# aparture_v1.net
KiCad netlist of a schematic drawn in EAGLE
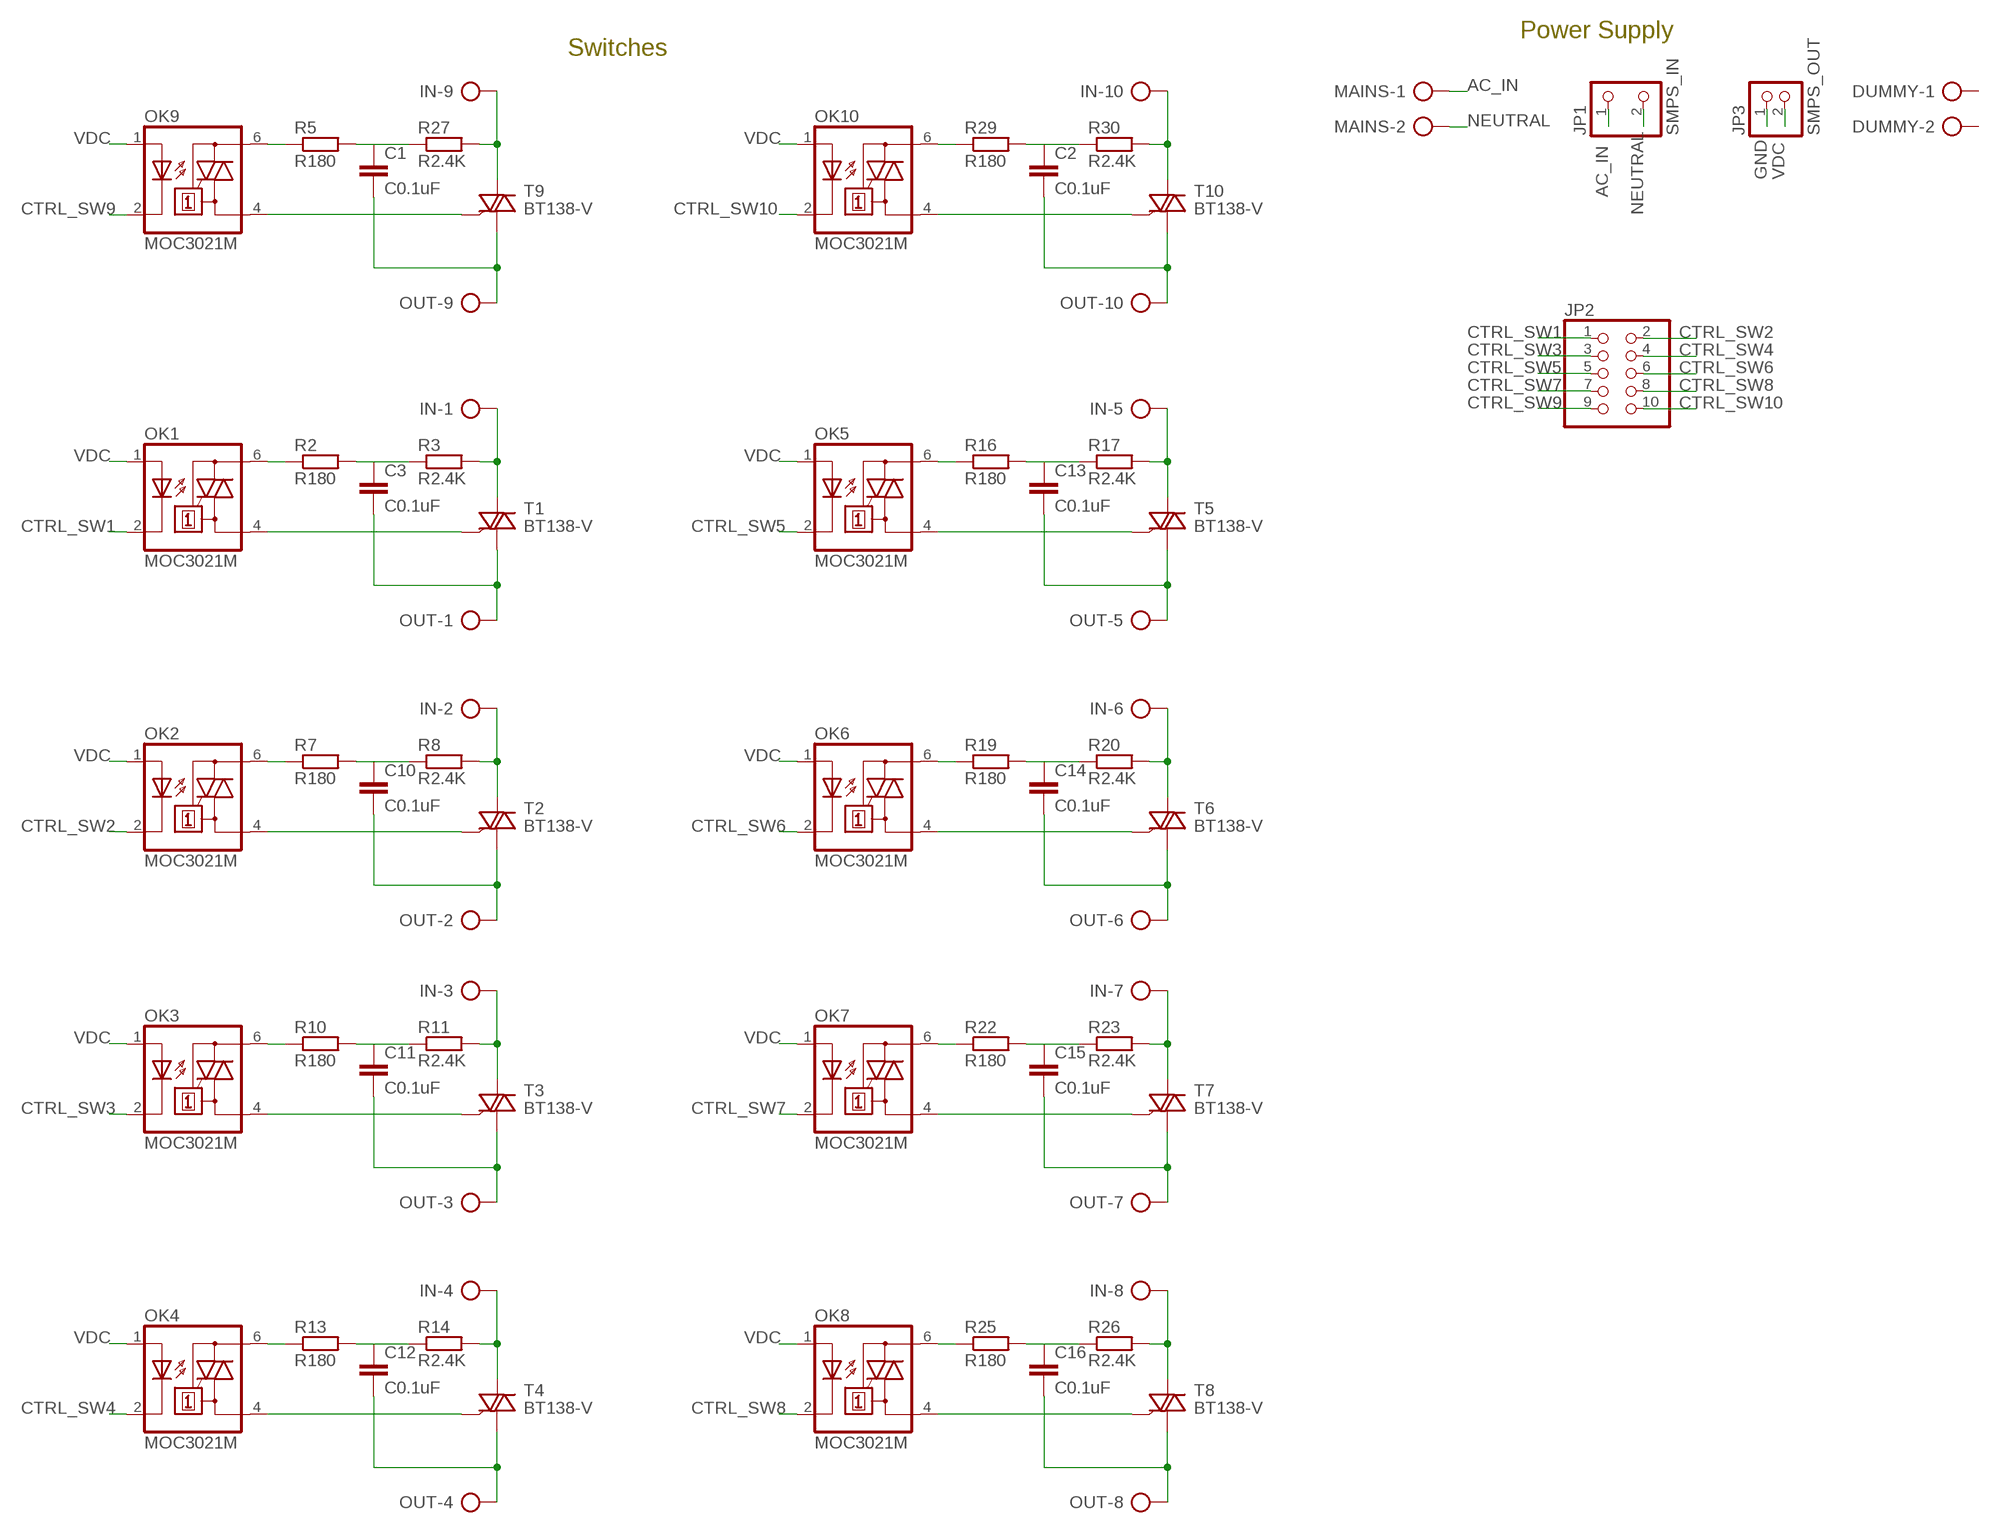
[diagram p0: schematic, sheet 1]

(export (version "E")
  (design (tool "Eeschema 10.0.6"))
  (components
    (comp (ref "C1")
      (value "C0.1uF")
      (footprint "eagle-import:C0805")
      (libsource (lib "eagle-import") (part "C-EUC0805"))
    )
    (comp (ref "C2")
      (value "C0.1uF")
      (footprint "eagle-import:C0805")
      (libsource (lib "eagle-import") (part "C-EUC0805"))
    )
    (comp (ref "C3")
      (value "C0.1uF")
      (footprint "eagle-import:C0805")
      (libsource (lib "eagle-import") (part "C-EUC0805"))
    )
    (comp (ref "C10")
      (value "C0.1uF")
      (footprint "eagle-import:C0805")
      (libsource (lib "eagle-import") (part "C-EUC0805"))
    )
    (comp (ref "C11")
      (value "C0.1uF")
      (footprint "eagle-import:C0805")
      (libsource (lib "eagle-import") (part "C-EUC0805"))
    )
    (comp (ref "C12")
      (value "C0.1uF")
      (footprint "eagle-import:C0805")
      (libsource (lib "eagle-import") (part "C-EUC0805"))
    )
    (comp (ref "C13")
      (value "C0.1uF")
      (footprint "eagle-import:C0805")
      (libsource (lib "eagle-import") (part "C-EUC0805"))
    )
    (comp (ref "C14")
      (value "C0.1uF")
      (footprint "eagle-import:C0805")
      (libsource (lib "eagle-import") (part "C-EUC0805"))
    )
    (comp (ref "C15")
      (value "C0.1uF")
      (footprint "eagle-import:C0805")
      (libsource (lib "eagle-import") (part "C-EUC0805"))
    )
    (comp (ref "C16")
      (value "C0.1uF")
      (footprint "eagle-import:C0805")
      (libsource (lib "eagle-import") (part "C-EUC0805"))
    )
    (comp (ref "DUMMY")
      (value "AK300/2")
      (footprint "eagle-import:AK300_2")
      (fields (field (name "OC_FARNELL") "unknown") (field (name "OC_NEWARK") "unknown"))
      (libsource (lib "eagle-import") (part "AK300/2"))
    )
    (comp (ref "IN")
      (value "AK300/10")
      (footprint "eagle-import:AK300_10")
      (libsource (lib "eagle-import") (part "AK300/10"))
    )
    (comp (ref "JP1")
      (value "SMPS_IN")
      (footprint "eagle-import:SMPS_IN")
      (libsource (lib "eagle-import") (part "SMPS_IN"))
    )
    (comp (ref "JP2")
      (value "PINHD-2X5")
      (footprint "eagle-import:2X05")
      (libsource (lib "eagle-import") (part "PINHD-2X5"))
    )
    (comp (ref "JP3")
      (value "SMPS_OUT")
      (footprint "eagle-import:1X02")
      (libsource (lib "eagle-import") (part "PINHD-1X2"))
    )
    (comp (ref "MAINS")
      (value "AK300/2")
      (footprint "eagle-import:AK300_2")
      (libsource (lib "eagle-import") (part "AK300/2"))
    )
    (comp (ref "OK1")
      (value "MOC3021M")
      (footprint "eagle-import:DIL06")
      (fields (field (name "MF") "FAIRCHILD SEMICONDUCTOR") (field (name "MPN") "MOC3021-M"))
      (libsource (lib "eagle-import") (part "MOC30M21"))
    )
    (comp (ref "OK2")
      (value "MOC3021M")
      (footprint "eagle-import:DIL06")
      (fields (field (name "MF") "FAIRCHILD SEMICONDUCTOR") (field (name "MPN") "MOC3021-M"))
      (libsource (lib "eagle-import") (part "MOC30M21"))
    )
    (comp (ref "OK3")
      (value "MOC3021M")
      (footprint "eagle-import:DIL06")
      (fields (field (name "MF") "FAIRCHILD SEMICONDUCTOR") (field (name "MPN") "MOC3021-M"))
      (libsource (lib "eagle-import") (part "MOC30M21"))
    )
    (comp (ref "OK4")
      (value "MOC3021M")
      (footprint "eagle-import:DIL06")
      (fields (field (name "MF") "FAIRCHILD SEMICONDUCTOR") (field (name "MPN") "MOC3021-M"))
      (libsource (lib "eagle-import") (part "MOC30M21"))
    )
    (comp (ref "OK5")
      (value "MOC3021M")
      (footprint "eagle-import:DIL06")
      (fields (field (name "MF") "FAIRCHILD SEMICONDUCTOR") (field (name "MPN") "MOC3021-M"))
      (libsource (lib "eagle-import") (part "MOC30M21"))
    )
    (comp (ref "OK6")
      (value "MOC3021M")
      (footprint "eagle-import:DIL06")
      (fields (field (name "MF") "FAIRCHILD SEMICONDUCTOR") (field (name "MPN") "MOC3021-M"))
      (libsource (lib "eagle-import") (part "MOC30M21"))
    )
    (comp (ref "OK7")
      (value "MOC3021M")
      (footprint "eagle-import:DIL06")
      (fields (field (name "MF") "FAIRCHILD SEMICONDUCTOR") (field (name "MPN") "MOC3021-M"))
      (libsource (lib "eagle-import") (part "MOC30M21"))
    )
    (comp (ref "OK8")
      (value "MOC3021M")
      (footprint "eagle-import:DIL06")
      (fields (field (name "MF") "FAIRCHILD SEMICONDUCTOR") (field (name "MPN") "MOC3021-M"))
      (libsource (lib "eagle-import") (part "MOC30M21"))
    )
    (comp (ref "OK9")
      (value "MOC3021M")
      (footprint "eagle-import:DIL06")
      (fields (field (name "MF") "FAIRCHILD SEMICONDUCTOR") (field (name "MPN") "MOC3021-M"))
      (libsource (lib "eagle-import") (part "MOC30M21"))
    )
    (comp (ref "OK10")
      (value "MOC3021M")
      (footprint "eagle-import:DIL06")
      (fields (field (name "MF") "FAIRCHILD SEMICONDUCTOR") (field (name "MPN") "MOC3021-M"))
      (libsource (lib "eagle-import") (part "MOC30M21"))
    )
    (comp (ref "OUT")
      (value "AK300/10")
      (footprint "eagle-import:AK300_10")
      (libsource (lib "eagle-import") (part "AK300/10"))
    )
    (comp (ref "R2")
      (value "R180")
      (footprint "eagle-import:M0805")
      (libsource (lib "eagle-import") (part "R-EU_M0805"))
    )
    (comp (ref "R3")
      (value "R2.4K")
      (footprint "eagle-import:M0805")
      (libsource (lib "eagle-import") (part "R-EU_M0805"))
    )
    (comp (ref "R5")
      (value "R180")
      (footprint "eagle-import:M0805")
      (libsource (lib "eagle-import") (part "R-EU_M0805"))
    )
    (comp (ref "R7")
      (value "R180")
      (footprint "eagle-import:M0805")
      (libsource (lib "eagle-import") (part "R-EU_M0805"))
    )
    (comp (ref "R8")
      (value "R2.4K")
      (footprint "eagle-import:M0805")
      (libsource (lib "eagle-import") (part "R-EU_M0805"))
    )
    (comp (ref "R10")
      (value "R180")
      (footprint "eagle-import:M0805")
      (libsource (lib "eagle-import") (part "R-EU_M0805"))
    )
    (comp (ref "R11")
      (value "R2.4K")
      (footprint "eagle-import:M0805")
      (libsource (lib "eagle-import") (part "R-EU_M0805"))
    )
    (comp (ref "R13")
      (value "R180")
      (footprint "eagle-import:M0805")
      (libsource (lib "eagle-import") (part "R-EU_M0805"))
    )
    (comp (ref "R14")
      (value "R2.4K")
      (footprint "eagle-import:M0805")
      (libsource (lib "eagle-import") (part "R-EU_M0805"))
    )
    (comp (ref "R16")
      (value "R180")
      (footprint "eagle-import:M0805")
      (libsource (lib "eagle-import") (part "R-EU_M0805"))
    )
    (comp (ref "R17")
      (value "R2.4K")
      (footprint "eagle-import:M0805")
      (libsource (lib "eagle-import") (part "R-EU_M0805"))
    )
    (comp (ref "R19")
      (value "R180")
      (footprint "eagle-import:M0805")
      (libsource (lib "eagle-import") (part "R-EU_M0805"))
    )
    (comp (ref "R20")
      (value "R2.4K")
      (footprint "eagle-import:M0805")
      (libsource (lib "eagle-import") (part "R-EU_M0805"))
    )
    (comp (ref "R22")
      (value "R180")
      (footprint "eagle-import:M0805")
      (libsource (lib "eagle-import") (part "R-EU_M0805"))
    )
    (comp (ref "R23")
      (value "R2.4K")
      (footprint "eagle-import:M0805")
      (libsource (lib "eagle-import") (part "R-EU_M0805"))
    )
    (comp (ref "R25")
      (value "R180")
      (footprint "eagle-import:M0805")
      (libsource (lib "eagle-import") (part "R-EU_M0805"))
    )
    (comp (ref "R26")
      (value "R2.4K")
      (footprint "eagle-import:M0805")
      (libsource (lib "eagle-import") (part "R-EU_M0805"))
    )
    (comp (ref "R27")
      (value "R2.4K")
      (footprint "eagle-import:M0805")
      (libsource (lib "eagle-import") (part "R-EU_M0805"))
    )
    (comp (ref "R29")
      (value "R180")
      (footprint "eagle-import:M0805")
      (libsource (lib "eagle-import") (part "R-EU_M0805"))
    )
    (comp (ref "R30")
      (value "R2.4K")
      (footprint "eagle-import:M0805")
      (libsource (lib "eagle-import") (part "R-EU_M0805"))
    )
    (comp (ref "T1")
      (value "BT138-V")
      (footprint "eagle-import:TO220BV")
      (libsource (lib "eagle-import") (part "BT138-V"))
    )
    (comp (ref "T2")
      (value "BT138-V")
      (footprint "eagle-import:TO220BV")
      (libsource (lib "eagle-import") (part "BT138-V"))
    )
    (comp (ref "T3")
      (value "BT138-V")
      (footprint "eagle-import:TO220BV")
      (libsource (lib "eagle-import") (part "BT138-V"))
    )
    (comp (ref "T4")
      (value "BT138-V")
      (footprint "eagle-import:TO220BV")
      (libsource (lib "eagle-import") (part "BT138-V"))
    )
    (comp (ref "T5")
      (value "BT138-V")
      (footprint "eagle-import:TO220BV")
      (libsource (lib "eagle-import") (part "BT138-V"))
    )
    (comp (ref "T6")
      (value "BT138-V")
      (footprint "eagle-import:TO220BV")
      (libsource (lib "eagle-import") (part "BT138-V"))
    )
    (comp (ref "T7")
      (value "BT138-V")
      (footprint "eagle-import:TO220BV")
      (libsource (lib "eagle-import") (part "BT138-V"))
    )
    (comp (ref "T8")
      (value "BT138-V")
      (footprint "eagle-import:TO220BV")
      (libsource (lib "eagle-import") (part "BT138-V"))
    )
    (comp (ref "T9")
      (value "BT138-V")
      (footprint "eagle-import:TO220BV")
      (libsource (lib "eagle-import") (part "BT138-V"))
    )
    (comp (ref "T10")
      (value "BT138-V")
      (footprint "eagle-import:TO220BV")
      (libsource (lib "eagle-import") (part "BT138-V"))
    )
  )
  (nets
    (net (code "1") (name "/AC_IN") (class "Default")
      (node (ref "JP1") (pin "1") (pinfunction "1_1") (pintype "passive"))
      (node (ref "MAINS") (pin "1") (pinfunction "KL_1") (pintype "passive"))
    )
    (net (code "2") (name "/CTRL_SW1") (class "Default")
      (node (ref "JP2") (pin "1") (pinfunction "1_1") (pintype "passive"))
      (node (ref "OK1") (pin "2") (pinfunction "C_2") (pintype "passive"))
    )
    (net (code "3") (name "/CTRL_SW2") (class "Default")
      (node (ref "JP2") (pin "2") (pinfunction "2_2") (pintype "passive"))
      (node (ref "OK2") (pin "2") (pinfunction "C_2") (pintype "passive"))
    )
    (net (code "4") (name "/CTRL_SW3") (class "Default")
      (node (ref "JP2") (pin "3") (pinfunction "3_3") (pintype "passive"))
      (node (ref "OK3") (pin "2") (pinfunction "C_2") (pintype "passive"))
    )
    (net (code "5") (name "/CTRL_SW4") (class "Default")
      (node (ref "JP2") (pin "4") (pinfunction "4_4") (pintype "passive"))
      (node (ref "OK4") (pin "2") (pinfunction "C_2") (pintype "passive"))
    )
    (net (code "6") (name "/CTRL_SW5") (class "Default")
      (node (ref "JP2") (pin "5") (pinfunction "5_5") (pintype "passive"))
      (node (ref "OK5") (pin "2") (pinfunction "C_2") (pintype "passive"))
    )
    (net (code "7") (name "/CTRL_SW6") (class "Default")
      (node (ref "JP2") (pin "6") (pinfunction "6_6") (pintype "passive"))
      (node (ref "OK6") (pin "2") (pinfunction "C_2") (pintype "passive"))
    )
    (net (code "8") (name "/CTRL_SW7") (class "Default")
      (node (ref "JP2") (pin "7") (pinfunction "7_7") (pintype "passive"))
      (node (ref "OK7") (pin "2") (pinfunction "C_2") (pintype "passive"))
    )
    (net (code "9") (name "/CTRL_SW8") (class "Default")
      (node (ref "JP2") (pin "8") (pinfunction "8_8") (pintype "passive"))
      (node (ref "OK8") (pin "2") (pinfunction "C_2") (pintype "passive"))
    )
    (net (code "10") (name "/CTRL_SW9") (class "Default")
      (node (ref "JP2") (pin "9") (pinfunction "9_9") (pintype "passive"))
      (node (ref "OK9") (pin "2") (pinfunction "C_2") (pintype "passive"))
    )
    (net (code "11") (name "/CTRL_SW10") (class "Default")
      (node (ref "JP2") (pin "10") (pinfunction "10_10") (pintype "passive"))
      (node (ref "OK10") (pin "2") (pinfunction "C_2") (pintype "passive"))
    )
    (net (code "12") (name "/GND") (class "Default")
      (node (ref "JP3") (pin "1") (pinfunction "1_1") (pintype "passive"))
    )
    (net (code "13") (name "/NEUTRAL") (class "Default")
      (node (ref "JP1") (pin "2") (pinfunction "2_2") (pintype "passive"))
      (node (ref "MAINS") (pin "2") (pinfunction "KL_2") (pintype "passive"))
    )
    (net (code "14") (name "/VDC") (class "Default")
      (node (ref "JP3") (pin "2") (pinfunction "2_2") (pintype "passive"))
      (node (ref "OK1") (pin "1") (pinfunction "A_1") (pintype "passive"))
      (node (ref "OK10") (pin "1") (pinfunction "A_1") (pintype "passive"))
      (node (ref "OK2") (pin "1") (pinfunction "A_1") (pintype "passive"))
      (node (ref "OK3") (pin "1") (pinfunction "A_1") (pintype "passive"))
      (node (ref "OK4") (pin "1") (pinfunction "A_1") (pintype "passive"))
      (node (ref "OK5") (pin "1") (pinfunction "A_1") (pintype "passive"))
      (node (ref "OK6") (pin "1") (pinfunction "A_1") (pintype "passive"))
      (node (ref "OK7") (pin "1") (pinfunction "A_1") (pintype "passive"))
      (node (ref "OK8") (pin "1") (pinfunction "A_1") (pintype "passive"))
      (node (ref "OK9") (pin "1") (pinfunction "A_1") (pintype "passive"))
    )
    (net (code "15") (name "Net-(C1-Pad1)") (class "Default")
      (node (ref "C1") (pin "1") (pinfunction "1_1") (pintype "passive"))
      (node (ref "R27") (pin "1") (pinfunction "1_1") (pintype "passive"))
      (node (ref "R5") (pin "2") (pinfunction "2_2") (pintype "passive"))
    )
    (net (code "16") (name "Net-(C2-Pad1)") (class "Default")
      (node (ref "C2") (pin "1") (pinfunction "1_1") (pintype "passive"))
      (node (ref "R29") (pin "2") (pinfunction "2_2") (pintype "passive"))
      (node (ref "R30") (pin "1") (pinfunction "1_1") (pintype "passive"))
    )
    (net (code "17") (name "Net-(C3-Pad1)") (class "Default")
      (node (ref "C3") (pin "1") (pinfunction "1_1") (pintype "passive"))
      (node (ref "R2") (pin "2") (pinfunction "2_2") (pintype "passive"))
      (node (ref "R3") (pin "1") (pinfunction "1_1") (pintype "passive"))
    )
    (net (code "18") (name "Net-(C10-Pad1)") (class "Default")
      (node (ref "C10") (pin "1") (pinfunction "1_1") (pintype "passive"))
      (node (ref "R7") (pin "2") (pinfunction "2_2") (pintype "passive"))
      (node (ref "R8") (pin "1") (pinfunction "1_1") (pintype "passive"))
    )
    (net (code "19") (name "Net-(C11-Pad1)") (class "Default")
      (node (ref "C11") (pin "1") (pinfunction "1_1") (pintype "passive"))
      (node (ref "R10") (pin "2") (pinfunction "2_2") (pintype "passive"))
      (node (ref "R11") (pin "1") (pinfunction "1_1") (pintype "passive"))
    )
    (net (code "20") (name "Net-(C12-Pad1)") (class "Default")
      (node (ref "C12") (pin "1") (pinfunction "1_1") (pintype "passive"))
      (node (ref "R13") (pin "2") (pinfunction "2_2") (pintype "passive"))
      (node (ref "R14") (pin "1") (pinfunction "1_1") (pintype "passive"))
    )
    (net (code "21") (name "Net-(C13-Pad1)") (class "Default")
      (node (ref "C13") (pin "1") (pinfunction "1_1") (pintype "passive"))
      (node (ref "R16") (pin "2") (pinfunction "2_2") (pintype "passive"))
      (node (ref "R17") (pin "1") (pinfunction "1_1") (pintype "passive"))
    )
    (net (code "22") (name "Net-(C14-Pad1)") (class "Default")
      (node (ref "C14") (pin "1") (pinfunction "1_1") (pintype "passive"))
      (node (ref "R19") (pin "2") (pinfunction "2_2") (pintype "passive"))
      (node (ref "R20") (pin "1") (pinfunction "1_1") (pintype "passive"))
    )
    (net (code "23") (name "Net-(C15-Pad1)") (class "Default")
      (node (ref "C15") (pin "1") (pinfunction "1_1") (pintype "passive"))
      (node (ref "R22") (pin "2") (pinfunction "2_2") (pintype "passive"))
      (node (ref "R23") (pin "1") (pinfunction "1_1") (pintype "passive"))
    )
    (net (code "24") (name "Net-(C16-Pad1)") (class "Default")
      (node (ref "C16") (pin "1") (pinfunction "1_1") (pintype "passive"))
      (node (ref "R25") (pin "2") (pinfunction "2_2") (pintype "passive"))
      (node (ref "R26") (pin "1") (pinfunction "1_1") (pintype "passive"))
    )
    (net (code "25") (name "Net-(INA-KL)") (class "Default")
      (node (ref "IN") (pin "1") (pinfunction "KL_1") (pintype "passive"))
      (node (ref "R3") (pin "2") (pinfunction "2_2") (pintype "passive"))
      (node (ref "T1") (pin "T2") (pinfunction "A2_T2") (pintype "passive"))
    )
    (net (code "26") (name "Net-(INB-KL)") (class "Default")
      (node (ref "IN") (pin "10") (pinfunction "KL_10") (pintype "passive"))
      (node (ref "R30") (pin "2") (pinfunction "2_2") (pintype "passive"))
      (node (ref "T10") (pin "T2") (pinfunction "A2_T2") (pintype "passive"))
    )
    (net (code "27") (name "Net-(INC-KL)") (class "Default")
      (node (ref "IN") (pin "2") (pinfunction "KL_2") (pintype "passive"))
      (node (ref "R8") (pin "2") (pinfunction "2_2") (pintype "passive"))
      (node (ref "T2") (pin "T2") (pinfunction "A2_T2") (pintype "passive"))
    )
    (net (code "28") (name "Net-(IND-KL)") (class "Default")
      (node (ref "IN") (pin "3") (pinfunction "KL_3") (pintype "passive"))
      (node (ref "R11") (pin "2") (pinfunction "2_2") (pintype "passive"))
      (node (ref "T3") (pin "T2") (pinfunction "A2_T2") (pintype "passive"))
    )
    (net (code "29") (name "Net-(INE-KL)") (class "Default")
      (node (ref "IN") (pin "4") (pinfunction "KL_4") (pintype "passive"))
      (node (ref "R14") (pin "2") (pinfunction "2_2") (pintype "passive"))
      (node (ref "T4") (pin "T2") (pinfunction "A2_T2") (pintype "passive"))
    )
    (net (code "30") (name "Net-(INF-KL)") (class "Default")
      (node (ref "IN") (pin "5") (pinfunction "KL_5") (pintype "passive"))
      (node (ref "R17") (pin "2") (pinfunction "2_2") (pintype "passive"))
      (node (ref "T5") (pin "T2") (pinfunction "A2_T2") (pintype "passive"))
    )
    (net (code "31") (name "Net-(ING-KL)") (class "Default")
      (node (ref "IN") (pin "6") (pinfunction "KL_6") (pintype "passive"))
      (node (ref "R20") (pin "2") (pinfunction "2_2") (pintype "passive"))
      (node (ref "T6") (pin "T2") (pinfunction "A2_T2") (pintype "passive"))
    )
    (net (code "32") (name "Net-(INH-KL)") (class "Default")
      (node (ref "IN") (pin "7") (pinfunction "KL_7") (pintype "passive"))
      (node (ref "R23") (pin "2") (pinfunction "2_2") (pintype "passive"))
      (node (ref "T7") (pin "T2") (pinfunction "A2_T2") (pintype "passive"))
    )
    (net (code "33") (name "Net-(INI-KL)") (class "Default")
      (node (ref "IN") (pin "8") (pinfunction "KL_8") (pintype "passive"))
      (node (ref "R26") (pin "2") (pinfunction "2_2") (pintype "passive"))
      (node (ref "T8") (pin "T2") (pinfunction "A2_T2") (pintype "passive"))
    )
    (net (code "34") (name "Net-(INJ-KL)") (class "Default")
      (node (ref "IN") (pin "9") (pinfunction "KL_9") (pintype "passive"))
      (node (ref "R27") (pin "2") (pinfunction "2_2") (pintype "passive"))
      (node (ref "T9") (pin "T2") (pinfunction "A2_T2") (pintype "passive"))
    )
    (net (code "35") (name "Net-(OK1-A1)") (class "Default")
      (node (ref "OK1") (pin "4") (pinfunction "A1_4") (pintype "passive"))
      (node (ref "T1") (pin "G") (pinfunction "G_G") (pintype "passive"))
    )
    (net (code "36") (name "Net-(OK1-A2)") (class "Default")
      (node (ref "OK1") (pin "6") (pinfunction "A2_6") (pintype "passive"))
      (node (ref "R2") (pin "1") (pinfunction "1_1") (pintype "passive"))
    )
    (net (code "37") (name "Net-(OK2-A1)") (class "Default")
      (node (ref "OK2") (pin "4") (pinfunction "A1_4") (pintype "passive"))
      (node (ref "T2") (pin "G") (pinfunction "G_G") (pintype "passive"))
    )
    (net (code "38") (name "Net-(OK2-A2)") (class "Default")
      (node (ref "OK2") (pin "6") (pinfunction "A2_6") (pintype "passive"))
      (node (ref "R7") (pin "1") (pinfunction "1_1") (pintype "passive"))
    )
    (net (code "39") (name "Net-(OK3-A1)") (class "Default")
      (node (ref "OK3") (pin "4") (pinfunction "A1_4") (pintype "passive"))
      (node (ref "T3") (pin "G") (pinfunction "G_G") (pintype "passive"))
    )
    (net (code "40") (name "Net-(OK3-A2)") (class "Default")
      (node (ref "OK3") (pin "6") (pinfunction "A2_6") (pintype "passive"))
      (node (ref "R10") (pin "1") (pinfunction "1_1") (pintype "passive"))
    )
    (net (code "41") (name "Net-(OK4-A1)") (class "Default")
      (node (ref "OK4") (pin "4") (pinfunction "A1_4") (pintype "passive"))
      (node (ref "T4") (pin "G") (pinfunction "G_G") (pintype "passive"))
    )
    (net (code "42") (name "Net-(OK4-A2)") (class "Default")
      (node (ref "OK4") (pin "6") (pinfunction "A2_6") (pintype "passive"))
      (node (ref "R13") (pin "1") (pinfunction "1_1") (pintype "passive"))
    )
    (net (code "43") (name "Net-(OK5-A1)") (class "Default")
      (node (ref "OK5") (pin "4") (pinfunction "A1_4") (pintype "passive"))
      (node (ref "T5") (pin "G") (pinfunction "G_G") (pintype "passive"))
    )
    (net (code "44") (name "Net-(OK5-A2)") (class "Default")
      (node (ref "OK5") (pin "6") (pinfunction "A2_6") (pintype "passive"))
      (node (ref "R16") (pin "1") (pinfunction "1_1") (pintype "passive"))
    )
    (net (code "45") (name "Net-(OK6-A1)") (class "Default")
      (node (ref "OK6") (pin "4") (pinfunction "A1_4") (pintype "passive"))
      (node (ref "T6") (pin "G") (pinfunction "G_G") (pintype "passive"))
    )
    (net (code "46") (name "Net-(OK6-A2)") (class "Default")
      (node (ref "OK6") (pin "6") (pinfunction "A2_6") (pintype "passive"))
      (node (ref "R19") (pin "1") (pinfunction "1_1") (pintype "passive"))
    )
    (net (code "47") (name "Net-(OK7-A1)") (class "Default")
      (node (ref "OK7") (pin "4") (pinfunction "A1_4") (pintype "passive"))
      (node (ref "T7") (pin "G") (pinfunction "G_G") (pintype "passive"))
    )
    (net (code "48") (name "Net-(OK7-A2)") (class "Default")
      (node (ref "OK7") (pin "6") (pinfunction "A2_6") (pintype "passive"))
      (node (ref "R22") (pin "1") (pinfunction "1_1") (pintype "passive"))
    )
    (net (code "49") (name "Net-(OK8-A1)") (class "Default")
      (node (ref "OK8") (pin "4") (pinfunction "A1_4") (pintype "passive"))
      (node (ref "T8") (pin "G") (pinfunction "G_G") (pintype "passive"))
    )
    (net (code "50") (name "Net-(OK8-A2)") (class "Default")
      (node (ref "OK8") (pin "6") (pinfunction "A2_6") (pintype "passive"))
      (node (ref "R25") (pin "1") (pinfunction "1_1") (pintype "passive"))
    )
    (net (code "51") (name "Net-(OK9-A1)") (class "Default")
      (node (ref "OK9") (pin "4") (pinfunction "A1_4") (pintype "passive"))
      (node (ref "T9") (pin "G") (pinfunction "G_G") (pintype "passive"))
    )
    (net (code "52") (name "Net-(OK9-A2)") (class "Default")
      (node (ref "OK9") (pin "6") (pinfunction "A2_6") (pintype "passive"))
      (node (ref "R5") (pin "1") (pinfunction "1_1") (pintype "passive"))
    )
    (net (code "53") (name "Net-(OK10-A1)") (class "Default")
      (node (ref "OK10") (pin "4") (pinfunction "A1_4") (pintype "passive"))
      (node (ref "T10") (pin "G") (pinfunction "G_G") (pintype "passive"))
    )
    (net (code "54") (name "Net-(OK10-A2)") (class "Default")
      (node (ref "OK10") (pin "6") (pinfunction "A2_6") (pintype "passive"))
      (node (ref "R29") (pin "1") (pinfunction "1_1") (pintype "passive"))
    )
    (net (code "55") (name "Net-(OUTA-KL)") (class "Default")
      (node (ref "C3") (pin "2") (pinfunction "2_2") (pintype "passive"))
      (node (ref "OUT") (pin "1") (pinfunction "KL_1") (pintype "passive"))
      (node (ref "T1") (pin "T1") (pinfunction "A1_T1") (pintype "passive"))
    )
    (net (code "56") (name "Net-(OUTB-KL)") (class "Default")
      (node (ref "C2") (pin "2") (pinfunction "2_2") (pintype "passive"))
      (node (ref "OUT") (pin "10") (pinfunction "KL_10") (pintype "passive"))
      (node (ref "T10") (pin "T1") (pinfunction "A1_T1") (pintype "passive"))
    )
    (net (code "57") (name "Net-(OUTC-KL)") (class "Default")
      (node (ref "C10") (pin "2") (pinfunction "2_2") (pintype "passive"))
      (node (ref "OUT") (pin "2") (pinfunction "KL_2") (pintype "passive"))
      (node (ref "T2") (pin "T1") (pinfunction "A1_T1") (pintype "passive"))
    )
    (net (code "58") (name "Net-(OUTD-KL)") (class "Default")
      (node (ref "C11") (pin "2") (pinfunction "2_2") (pintype "passive"))
      (node (ref "OUT") (pin "3") (pinfunction "KL_3") (pintype "passive"))
      (node (ref "T3") (pin "T1") (pinfunction "A1_T1") (pintype "passive"))
    )
    (net (code "59") (name "Net-(OUTE-KL)") (class "Default")
      (node (ref "C12") (pin "2") (pinfunction "2_2") (pintype "passive"))
      (node (ref "OUT") (pin "4") (pinfunction "KL_4") (pintype "passive"))
      (node (ref "T4") (pin "T1") (pinfunction "A1_T1") (pintype "passive"))
    )
    (net (code "60") (name "Net-(OUTF-KL)") (class "Default")
      (node (ref "C13") (pin "2") (pinfunction "2_2") (pintype "passive"))
      (node (ref "OUT") (pin "5") (pinfunction "KL_5") (pintype "passive"))
      (node (ref "T5") (pin "T1") (pinfunction "A1_T1") (pintype "passive"))
    )
    (net (code "61") (name "Net-(OUTG-KL)") (class "Default")
      (node (ref "C14") (pin "2") (pinfunction "2_2") (pintype "passive"))
      (node (ref "OUT") (pin "6") (pinfunction "KL_6") (pintype "passive"))
      (node (ref "T6") (pin "T1") (pinfunction "A1_T1") (pintype "passive"))
    )
    (net (code "62") (name "Net-(OUTH-KL)") (class "Default")
      (node (ref "C15") (pin "2") (pinfunction "2_2") (pintype "passive"))
      (node (ref "OUT") (pin "7") (pinfunction "KL_7") (pintype "passive"))
      (node (ref "T7") (pin "T1") (pinfunction "A1_T1") (pintype "passive"))
    )
    (net (code "63") (name "Net-(OUTI-KL)") (class "Default")
      (node (ref "C16") (pin "2") (pinfunction "2_2") (pintype "passive"))
      (node (ref "OUT") (pin "8") (pinfunction "KL_8") (pintype "passive"))
      (node (ref "T8") (pin "T1") (pinfunction "A1_T1") (pintype "passive"))
    )
    (net (code "64") (name "Net-(OUTJ-KL)") (class "Default")
      (node (ref "C1") (pin "2") (pinfunction "2_2") (pintype "passive"))
      (node (ref "OUT") (pin "9") (pinfunction "KL_9") (pintype "passive"))
      (node (ref "T9") (pin "T1") (pinfunction "A1_T1") (pintype "passive"))
    )
    (net (code "65") (name "unconnected-(DUMMYA-KL-Pad1)") (class "Default")
      (node (ref "DUMMY") (pin "1") (pinfunction "KL_1") (pintype "passive"))
    )
    (net (code "66") (name "unconnected-(DUMMYB-KL-Pad2)") (class "Default")
      (node (ref "DUMMY") (pin "2") (pinfunction "KL_2") (pintype "passive"))
    )
  )
)
